# PCA_0011_Mini_Breakout_REV_B.net
KiCad netlist of a schematic drawn in Altium Designer
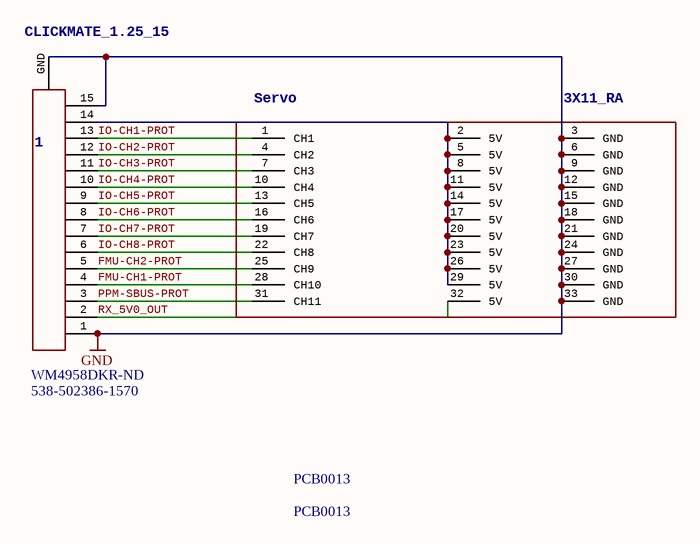
[diagram p0: PCA_0011_Mini Breakout_REV_B.SchDoc]

(export (version "E")
  (design (tool "Eeschema 10.0.6"))
  (components
    (comp (ref "1")
      (value "CLICKMATE_1.25_15")
      (footprint "CLICKMATE_H15")
      (description "Connector, Receptacle, 15Pos, 1.25MM, R/A, SMD, Tin")
      (fields
        (field (name "SUPPLIER PART NUMBER 1") "WM4958DKR-ND")
        (field (name "SUPPLIER PART NUMBER 2") "538-502386-1570")
        (field (name "3DR_PARTNO") "ECM0530")
      )
      (libsource (lib "pixhawk2") (part "CLICKMATE_1.25_15"))
    )
    (comp (ref "PCB0013")
      (value "PCB0013")
      (description "PCB,clickmate 15 to 0.1\" adaptor board,Board")
      (libsource (lib "lib_pixhawk") (part "PCB_0013"))
    )
    (comp (ref "Servo")
      (value "3X11_RA")
      (footprint "3X11RA")
      (description "11 x 3 RA Servo header, gold plated.")
      (fields (field (name "PARTNO") "894-80-042-20-001101") (field (name "3DR_PARTNO") "UNKNOWN"))
      (libsource (lib "pixhawk2") (part "3X11_RA"))
    )
  )
  (nets
    (net (code "1") (name "/FMU-CH1-PROT") (class "Default")
      (node (ref "1") (pin "4") (pinfunction "4_4") (pintype "passive"))
      (node (ref "Servo") (pin "28") (pinfunction "CH10_28") (pintype "passive"))
    )
    (net (code "2") (name "/FMU-CH2-PROT") (class "Default")
      (node (ref "1") (pin "5") (pinfunction "5_5") (pintype "passive"))
      (node (ref "Servo") (pin "25") (pinfunction "CH9_25") (pintype "passive"))
    )
    (net (code "3") (name "/IO-CH1-PROT") (class "Default")
      (node (ref "1") (pin "13") (pinfunction "13_13") (pintype "passive"))
      (node (ref "Servo") (pin "1") (pinfunction "CH1_1") (pintype "passive"))
    )
    (net (code "4") (name "/IO-CH2-PROT") (class "Default")
      (node (ref "1") (pin "12") (pinfunction "12_12") (pintype "passive"))
      (node (ref "Servo") (pin "4") (pinfunction "CH2_4") (pintype "passive"))
    )
    (net (code "5") (name "/IO-CH3-PROT") (class "Default")
      (node (ref "1") (pin "11") (pinfunction "11_11") (pintype "passive"))
      (node (ref "Servo") (pin "7") (pinfunction "CH3_7") (pintype "passive"))
    )
    (net (code "6") (name "/IO-CH4-PROT") (class "Default")
      (node (ref "1") (pin "10") (pinfunction "10_10") (pintype "passive"))
      (node (ref "Servo") (pin "10") (pinfunction "CH4_10") (pintype "passive"))
    )
    (net (code "7") (name "/IO-CH5-PROT") (class "Default")
      (node (ref "1") (pin "9") (pinfunction "9_9") (pintype "passive"))
      (node (ref "Servo") (pin "13") (pinfunction "CH5_13") (pintype "passive"))
    )
    (net (code "8") (name "/IO-CH6-PROT") (class "Default")
      (node (ref "1") (pin "8") (pinfunction "8_8") (pintype "passive"))
      (node (ref "Servo") (pin "16") (pinfunction "CH6_16") (pintype "passive"))
    )
    (net (code "9") (name "/IO-CH7-PROT") (class "Default")
      (node (ref "1") (pin "7") (pinfunction "7_7") (pintype "passive"))
      (node (ref "Servo") (pin "19") (pinfunction "CH7_19") (pintype "passive"))
    )
    (net (code "10") (name "/IO-CH8-PROT") (class "Default")
      (node (ref "1") (pin "6") (pinfunction "6_6") (pintype "passive"))
      (node (ref "Servo") (pin "22") (pinfunction "CH8_22") (pintype "passive"))
    )
    (net (code "11") (name "/PPM-SBUS-PROT") (class "Default")
      (node (ref "1") (pin "3") (pinfunction "3_3") (pintype "passive"))
      (node (ref "Servo") (pin "31") (pinfunction "CH11_31") (pintype "passive"))
    )
    (net (code "12") (name "/RX_5V0_OUT") (class "Default")
      (node (ref "1") (pin "2") (pinfunction "2_2") (pintype "passive"))
      (node (ref "Servo") (pin "32") (pinfunction "5V_32") (pintype "passive"))
    )
    (net (code "13") (name "GND") (class "Default")
      (node (ref "1") (pin "1") (pinfunction "1_1") (pintype "passive"))
      (node (ref "1") (pin "15") (pinfunction "15_15") (pintype "passive"))
      (node (ref "1") (pin "GND") (pinfunction "GND_GND") (pintype "passive"))
      (node (ref "Servo") (pin "12") (pinfunction "GND_12") (pintype "passive"))
      (node (ref "Servo") (pin "15") (pinfunction "GND_15") (pintype "passive"))
      (node (ref "Servo") (pin "18") (pinfunction "GND_18") (pintype "passive"))
      (node (ref "Servo") (pin "21") (pinfunction "GND_21") (pintype "passive"))
      (node (ref "Servo") (pin "24") (pinfunction "GND_24") (pintype "passive"))
      (node (ref "Servo") (pin "27") (pinfunction "GND_27") (pintype "passive"))
      (node (ref "Servo") (pin "3") (pinfunction "GND_3") (pintype "passive"))
      (node (ref "Servo") (pin "30") (pinfunction "GND_30") (pintype "passive"))
      (node (ref "Servo") (pin "33") (pinfunction "GND_33") (pintype "passive"))
      (node (ref "Servo") (pin "6") (pinfunction "GND_6") (pintype "passive"))
      (node (ref "Servo") (pin "9") (pinfunction "GND_9") (pintype "passive"))
    )
    (net (code "14") (name "Net-(1-Pad14)") (class "Default")
      (node (ref "1") (pin "14") (pinfunction "14_14") (pintype "passive"))
      (node (ref "Servo") (pin "11") (pinfunction "5V_11") (pintype "passive"))
      (node (ref "Servo") (pin "14") (pinfunction "5V_14") (pintype "passive"))
      (node (ref "Servo") (pin "17") (pinfunction "5V_17") (pintype "passive"))
      (node (ref "Servo") (pin "2") (pinfunction "5V_2") (pintype "passive"))
      (node (ref "Servo") (pin "20") (pinfunction "5V_20") (pintype "passive"))
      (node (ref "Servo") (pin "23") (pinfunction "5V_23") (pintype "passive"))
      (node (ref "Servo") (pin "26") (pinfunction "5V_26") (pintype "passive"))
      (node (ref "Servo") (pin "29") (pinfunction "5V_29") (pintype "passive"))
      (node (ref "Servo") (pin "5") (pinfunction "5V_5") (pintype "passive"))
      (node (ref "Servo") (pin "8") (pinfunction "5V_8") (pintype "passive"))
    )
  )
)
